# espduino-01.net
KiCad netlist of a schematic drawn in EAGLE
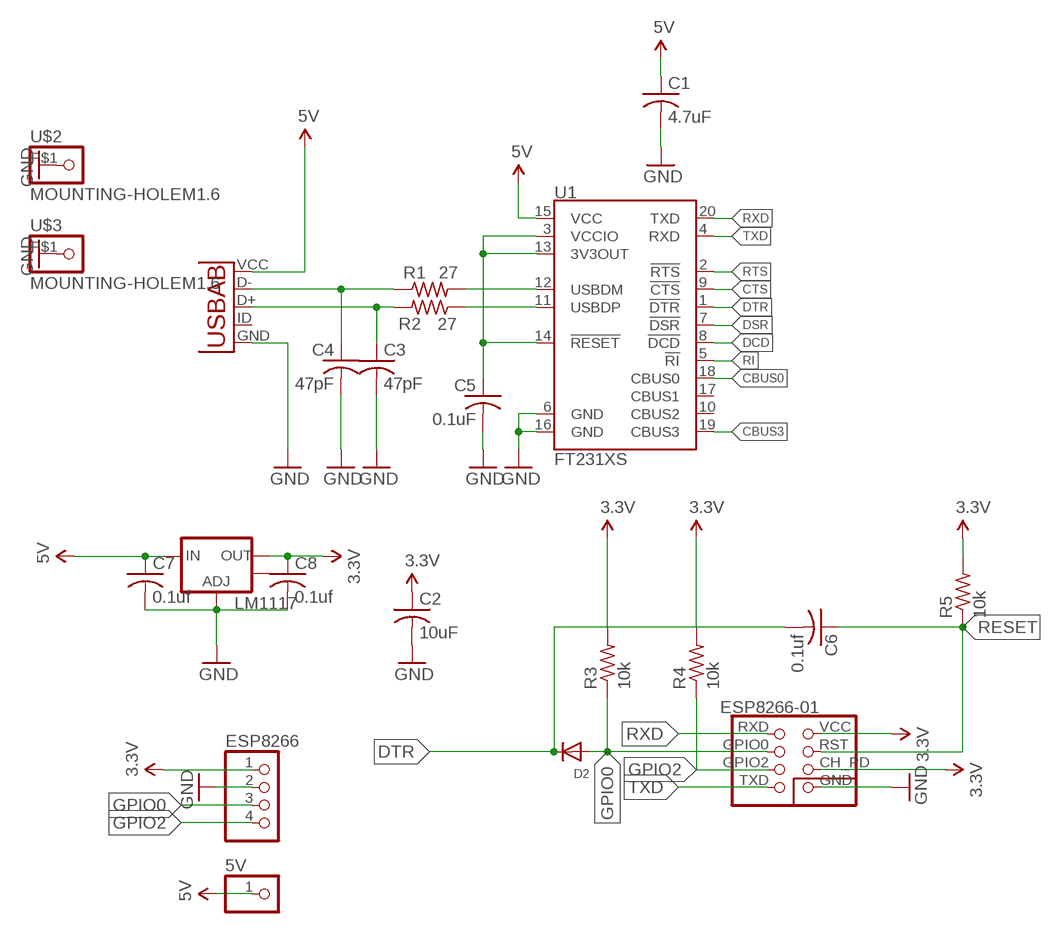
[diagram p0: schematic, sheet 1]

(export (version "E")
  (design (tool "Eeschema 10.0.6"))
  (components
    (comp (ref "5V")
      (value "PINHD-1X1")
      (footprint "eagle-import:1X01")
      (libsource (lib "eagle-import") (part "PINHD-1X1"))
    )
    (comp (ref "C1")
      (value "4.7uF")
      (footprint "eagle-import:C0603")
      (libsource (lib "eagle-import") (part "C-USC0603"))
    )
    (comp (ref "C2")
      (value "10uF")
      (footprint "eagle-import:C0603")
      (libsource (lib "eagle-import") (part "C-USC0603"))
    )
    (comp (ref "C3")
      (value "47pF")
      (footprint "eagle-import:C0603")
      (libsource (lib "eagle-import") (part "C-USC0603"))
    )
    (comp (ref "C4")
      (value "47pF")
      (footprint "eagle-import:C0603")
      (libsource (lib "eagle-import") (part "C-USC0603"))
    )
    (comp (ref "C5")
      (value "0.1uF")
      (footprint "eagle-import:C0603")
      (libsource (lib "eagle-import") (part "C-USC0603"))
    )
    (comp (ref "C6")
      (value "0.1uf")
      (footprint "eagle-import:C0603")
      (libsource (lib "eagle-import") (part "C-USC0603"))
    )
    (comp (ref "C7")
      (value "0.1uf")
      (footprint "eagle-import:C0603")
      (libsource (lib "eagle-import") (part "C-USC0603"))
    )
    (comp (ref "C8")
      (value "0.1uf")
      (footprint "eagle-import:C0603")
      (libsource (lib "eagle-import") (part "C-USC0603"))
    )
    (comp (ref "D2")
      (value "DIODESOT23_REFLOW")
      (footprint "eagle-import:SOT23-R")
      (libsource (lib "eagle-import") (part "DIODESOT23_REFLOW"))
    )
    (comp (ref "ESP8266")
      (value "PINHD-1X4")
      (footprint "eagle-import:1X04")
      (libsource (lib "eagle-import") (part "PINHD-1X4"))
    )
    (comp (ref "ESP8266-01")
      (value "ESP8266ESP8266-01-MIN")
      (footprint "eagle-import:ESP8266-01-MIN")
      (libsource (lib "eagle-import") (part "ESP8266ESP8266-01-MIN"))
    )
    (comp (ref "LM1117")
      (value "V_REG_LM1117SOT223")
      (footprint "eagle-import:SOT223")
      (libsource (lib "eagle-import") (part "V_REG_LM1117SOT223"))
    )
    (comp (ref "R1")
      (value "27")
      (footprint "eagle-import:R0603")
      (libsource (lib "eagle-import") (part "R-US_R0603"))
    )
    (comp (ref "R2")
      (value "27")
      (footprint "eagle-import:R0603")
      (libsource (lib "eagle-import") (part "R-US_R0603"))
    )
    (comp (ref "R3")
      (value "10k")
      (footprint "eagle-import:R0603")
      (libsource (lib "eagle-import") (part "R-US_R0603"))
    )
    (comp (ref "R4")
      (value "10k")
      (footprint "eagle-import:R0603")
      (libsource (lib "eagle-import") (part "R-US_R0603"))
    )
    (comp (ref "R5")
      (value "10k")
      (footprint "eagle-import:R0603")
      (libsource (lib "eagle-import") (part "R-US_R0603"))
    )
    (comp (ref "U$2")
      (value "MOUNTING-HOLEM1.6")
      (footprint "eagle-import:M1_6MOUNTING_HOLE")
      (libsource (lib "eagle-import") (part "MOUNTING-HOLEM1.6"))
    )
    (comp (ref "U$3")
      (value "MOUNTING-HOLEM1.6")
      (footprint "eagle-import:M1_6MOUNTING_HOLE")
      (libsource (lib "eagle-import") (part "MOUNTING-HOLEM1.6"))
    )
    (comp (ref "U1")
      (value "FT231XS")
      (footprint "eagle-import:SSOP20_L")
      (libsource (lib "eagle-import") (part "FT231XS"))
    )
    (comp (ref "U2")
      (value "USB-AB")
      (footprint "eagle-import:MICRO-USB-A01SB141B1")
      (libsource (lib "eagle-import") (part "USB-AB"))
    )
  )
  (nets
    (net (code "1") (name "3.3V") (class "Default")
      (node (ref "C2") (pin "1") (pinfunction "1_1") (pintype "passive"))
      (node (ref "C8") (pin "1") (pinfunction "1_1") (pintype "passive"))
      (node (ref "ESP8266") (pin "1") (pinfunction "1_1") (pintype "passive"))
      (node (ref "ESP8266-01") (pin "CH_PD") (pinfunction "CH_PD_CH_PD") (pintype "passive"))
      (node (ref "ESP8266-01") (pin "VCC") (pinfunction "VCC_VCC") (pintype "passive"))
      (node (ref "LM1117") (pin "2") (pinfunction "OUT_2") (pintype "output"))
      (node (ref "R3") (pin "2") (pinfunction "2_2") (pintype "passive"))
      (node (ref "R4") (pin "2") (pinfunction "2_2") (pintype "passive"))
      (node (ref "R5") (pin "2") (pinfunction "2_2") (pintype "passive"))
    )
    (net (code "2") (name "5V") (class "Default")
      (node (ref "5V") (pin "1") (pinfunction "1_1") (pintype "passive"))
      (node (ref "C1") (pin "1") (pinfunction "1_1") (pintype "passive"))
      (node (ref "C7") (pin "1") (pinfunction "1_1") (pintype "passive"))
      (node (ref "LM1117") (pin "3") (pinfunction "IN_3") (pintype "input"))
      (node (ref "U1") (pin "15") (pinfunction "VCC_15") (pintype "bidirectional"))
      (node (ref "U2") (pin "VCC") (pinfunction "VBUS_VCC") (pintype "bidirectional"))
    )
    (net (code "3") (name "CBUS0") (class "Default")
      (node (ref "U1") (pin "18") (pinfunction "CBUS0_18") (pintype "bidirectional"))
    )
    (net (code "4") (name "CBUS3") (class "Default")
      (node (ref "U1") (pin "19") (pinfunction "CBUS3_19") (pintype "bidirectional"))
    )
    (net (code "5") (name "CTS") (class "Default")
      (node (ref "U1") (pin "9") (pinfunction "~{CTS}_9") (pintype "bidirectional"))
    )
    (net (code "6") (name "DCD") (class "Default")
      (node (ref "U1") (pin "8") (pinfunction "~{DCD}_8") (pintype "bidirectional"))
    )
    (net (code "7") (name "DSR") (class "Default")
      (node (ref "U1") (pin "7") (pinfunction "~{DSR}_7") (pintype "bidirectional"))
    )
    (net (code "8") (name "DTR") (class "Default")
      (node (ref "C6") (pin "2") (pinfunction "2_2") (pintype "passive"))
      (node (ref "D2") (pin "3") (pinfunction "C_3") (pintype "passive"))
      (node (ref "U1") (pin "1") (pinfunction "~{DTR}_1") (pintype "bidirectional"))
    )
    (net (code "9") (name "GND") (class "Default")
      (node (ref "C1") (pin "2") (pinfunction "2_2") (pintype "passive"))
      (node (ref "C2") (pin "2") (pinfunction "2_2") (pintype "passive"))
      (node (ref "C3") (pin "2") (pinfunction "2_2") (pintype "passive"))
      (node (ref "C4") (pin "2") (pinfunction "2_2") (pintype "passive"))
      (node (ref "C5") (pin "2") (pinfunction "2_2") (pintype "passive"))
      (node (ref "C7") (pin "2") (pinfunction "2_2") (pintype "passive"))
      (node (ref "C8") (pin "2") (pinfunction "2_2") (pintype "passive"))
      (node (ref "ESP8266") (pin "2") (pinfunction "2_2") (pintype "passive"))
      (node (ref "ESP8266-01") (pin "GND") (pinfunction "GND_GND") (pintype "passive"))
      (node (ref "LM1117") (pin "1") (pinfunction "ADJ_1") (pintype "input"))
      (node (ref "U$2") (pin "P$1") (pinfunction "GND_P$1") (pintype "passive"))
      (node (ref "U$3") (pin "P$1") (pinfunction "GND_P$1") (pintype "passive"))
      (node (ref "U1") (pin "16") (pinfunction "GND_16") (pintype "bidirectional"))
      (node (ref "U1") (pin "6") (pinfunction "GND_6") (pintype "bidirectional"))
      (node (ref "U2") (pin "GND") (pinfunction "GND_GND") (pintype "bidirectional"))
    )
    (net (code "10") (name "GPIO0") (class "Default")
      (node (ref "D2") (pin "1") (pinfunction "A_1") (pintype "passive"))
      (node (ref "ESP8266") (pin "3") (pinfunction "3_3") (pintype "passive"))
      (node (ref "ESP8266-01") (pin "GPIO0") (pinfunction "GPIO0_GPIO0") (pintype "passive"))
      (node (ref "R3") (pin "1") (pinfunction "1_1") (pintype "passive"))
    )
    (net (code "11") (name "GPIO2") (class "Default")
      (node (ref "ESP8266") (pin "4") (pinfunction "4_4") (pintype "passive"))
      (node (ref "ESP8266-01") (pin "GPIO2") (pinfunction "GPIO2_GPIO2") (pintype "passive"))
      (node (ref "R4") (pin "1") (pinfunction "1_1") (pintype "passive"))
    )
    (net (code "12") (name "Net-(C3-Pad1)") (class "Default")
      (node (ref "C3") (pin "1") (pinfunction "1_1") (pintype "passive"))
      (node (ref "R2") (pin "2") (pinfunction "2_2") (pintype "passive"))
      (node (ref "U2") (pin "D+") (pinfunction "D+_D+") (pintype "bidirectional"))
    )
    (net (code "13") (name "Net-(C4-Pad1)") (class "Default")
      (node (ref "C4") (pin "1") (pinfunction "1_1") (pintype "passive"))
      (node (ref "R1") (pin "1") (pinfunction "1_1") (pintype "passive"))
      (node (ref "U2") (pin "D-") (pinfunction "D-_D-") (pintype "bidirectional"))
    )
    (net (code "14") (name "Net-(U1-3V3OUT)") (class "Default")
      (node (ref "C5") (pin "1") (pinfunction "1_1") (pintype "passive"))
      (node (ref "U1") (pin "13") (pinfunction "3V3OUT_13") (pintype "bidirectional"))
      (node (ref "U1") (pin "14") (pinfunction "~{RESET}_14") (pintype "bidirectional"))
      (node (ref "U1") (pin "3") (pinfunction "VCCIO_3") (pintype "bidirectional"))
    )
    (net (code "15") (name "Net-(U1-USBDM)") (class "Default")
      (node (ref "R1") (pin "2") (pinfunction "2_2") (pintype "passive"))
      (node (ref "U1") (pin "12") (pinfunction "USBDM_12") (pintype "bidirectional"))
    )
    (net (code "16") (name "Net-(U1-USBDP)") (class "Default")
      (node (ref "R2") (pin "1") (pinfunction "1_1") (pintype "passive"))
      (node (ref "U1") (pin "11") (pinfunction "USBDP_11") (pintype "bidirectional"))
    )
    (net (code "17") (name "RESET") (class "Default")
      (node (ref "C6") (pin "1") (pinfunction "1_1") (pintype "passive"))
      (node (ref "ESP8266-01") (pin "RST") (pinfunction "RST_RST") (pintype "passive"))
      (node (ref "R5") (pin "1") (pinfunction "1_1") (pintype "passive"))
    )
    (net (code "18") (name "RI") (class "Default")
      (node (ref "U1") (pin "5") (pinfunction "~{RI}_5") (pintype "bidirectional"))
    )
    (net (code "19") (name "RTS") (class "Default")
      (node (ref "U1") (pin "2") (pinfunction "~{RTS}_2") (pintype "bidirectional"))
    )
    (net (code "20") (name "RXD") (class "Default")
      (node (ref "ESP8266-01") (pin "RXD") (pinfunction "RXD_RXD") (pintype "passive"))
      (node (ref "U1") (pin "20") (pinfunction "TXD_20") (pintype "bidirectional"))
    )
    (net (code "21") (name "TXD") (class "Default")
      (node (ref "ESP8266-01") (pin "TXD") (pinfunction "TXD_TXD") (pintype "passive"))
      (node (ref "U1") (pin "4") (pinfunction "RXD_4") (pintype "bidirectional"))
    )
    (net (code "22") (name "unconnected-(LM1117-OUT-Pad4)") (class "Default")
      (node (ref "LM1117") (pin "4") (pinfunction "OUT_4") (pintype "output"))
    )
    (net (code "23") (name "unconnected-(U1-CBUS1-Pad17)") (class "Default")
      (node (ref "U1") (pin "17") (pinfunction "CBUS1_17") (pintype "bidirectional"))
    )
    (net (code "24") (name "unconnected-(U1-CBUS2-Pad10)") (class "Default")
      (node (ref "U1") (pin "10") (pinfunction "CBUS2_10") (pintype "bidirectional"))
    )
    (net (code "25") (name "unconnected-(U2-USBID-PadID)") (class "Default")
      (node (ref "U2") (pin "ID") (pinfunction "USBID_ID") (pintype "bidirectional"))
    )
  )
)
